# RefrigeradorLG.net
KiCad netlist of a schematic drawn in EAGLE
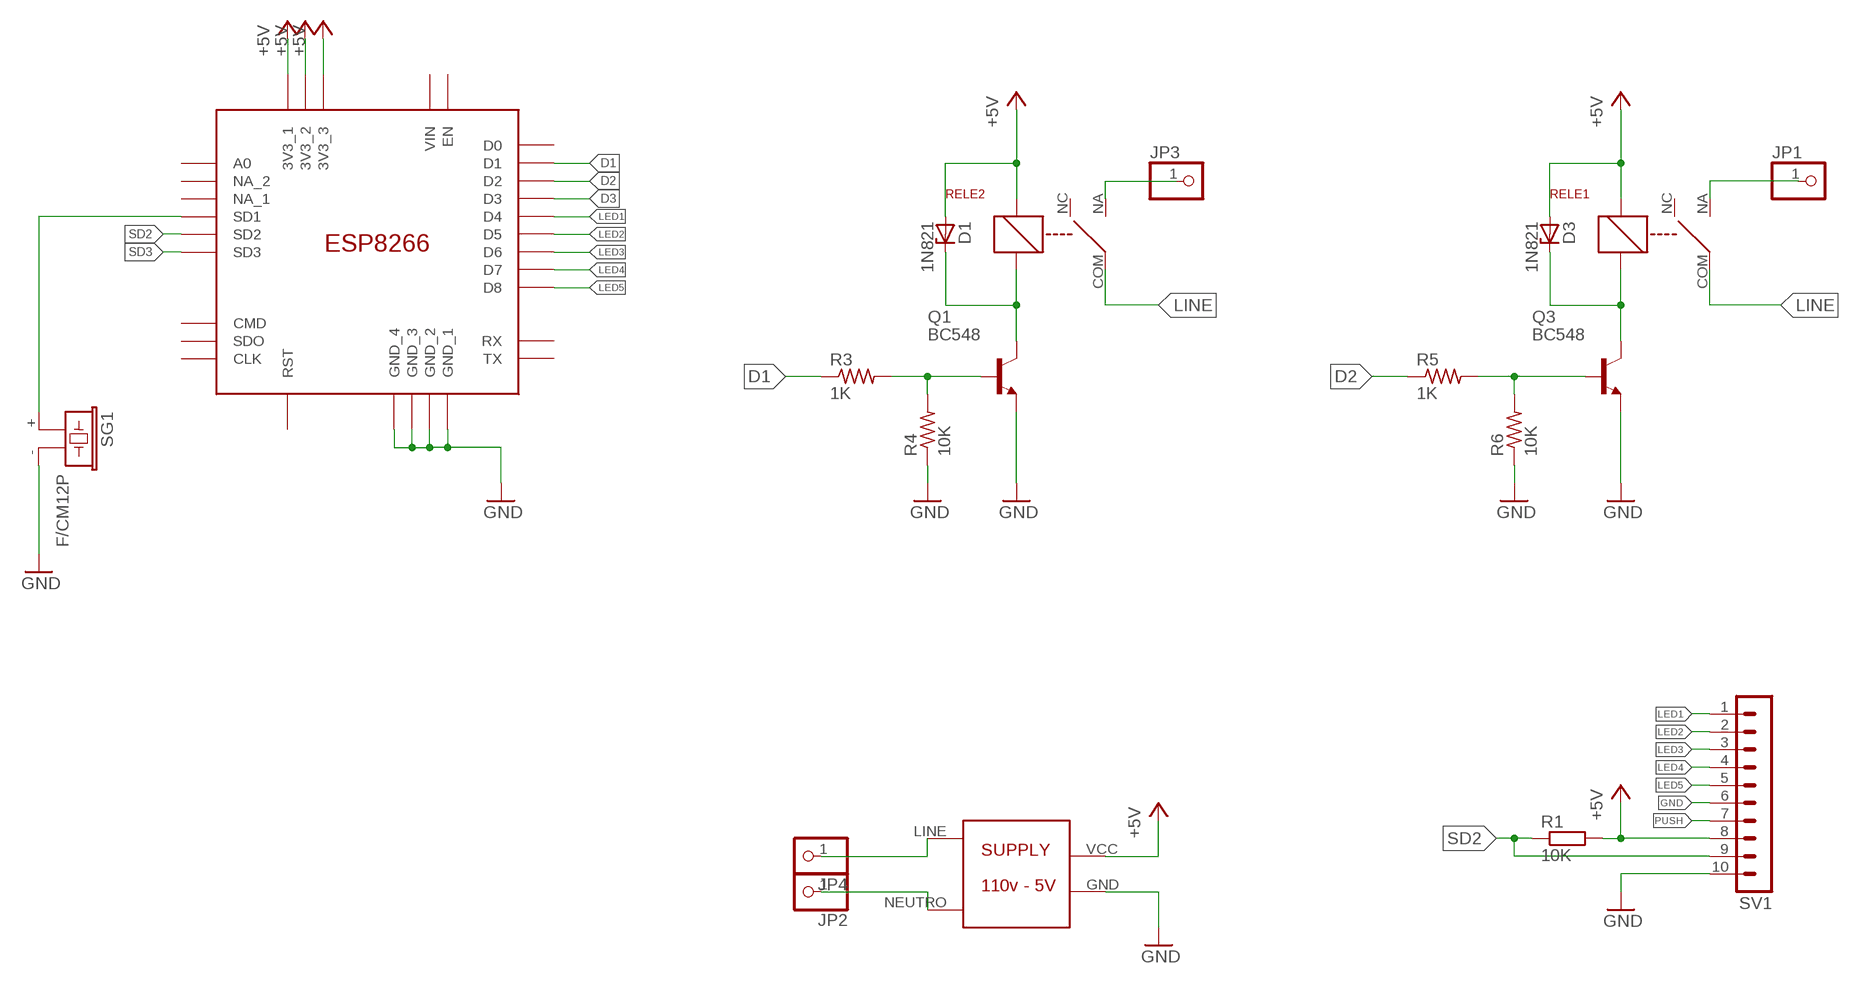
[diagram p0: schematic, sheet 1]

(export (version "E")
  (design (tool "Eeschema 10.0.6"))
  (components
    (comp (ref "D1")
      (value "1N821")
      (footprint "eagle-import:DO35Z10")
      (libsource (lib "eagle-import") (part "1N821"))
    )
    (comp (ref "D3")
      (value "1N821")
      (footprint "eagle-import:DO35Z10")
      (libsource (lib "eagle-import") (part "1N821"))
    )
    (comp (ref "ESP8266")
      (value "ESP8266")
      (footprint "eagle-import:ESP8266")
      (libsource (lib "eagle-import") (part "ESP8266"))
    )
    (comp (ref "JP1")
      (value "PINHD-1X1")
      (footprint "eagle-import:1X01")
      (libsource (lib "eagle-import") (part "PINHD-1X1"))
    )
    (comp (ref "JP2")
      (value "PINHD-1X1")
      (footprint "eagle-import:1X01")
      (libsource (lib "eagle-import") (part "PINHD-1X1"))
    )
    (comp (ref "JP3")
      (value "PINHD-1X1")
      (footprint "eagle-import:1X01")
      (libsource (lib "eagle-import") (part "PINHD-1X1"))
    )
    (comp (ref "JP4")
      (value "PINHD-1X1")
      (footprint "eagle-import:1X01")
      (libsource (lib "eagle-import") (part "PINHD-1X1"))
    )
    (comp (ref "Q1")
      (value "BC548")
      (footprint "eagle-import:TO92-EBC")
      (libsource (lib "eagle-import") (part "BC548"))
    )
    (comp (ref "Q3")
      (value "BC548")
      (footprint "eagle-import:TO92-EBC")
      (libsource (lib "eagle-import") (part "BC548"))
    )
    (comp (ref "R1")
      (value "10K")
      (footprint "eagle-import:0204_7")
      (libsource (lib "eagle-import") (part "R-EU_0204/7"))
    )
    (comp (ref "R3")
      (value "1K")
      (footprint "eagle-import:0204_7")
      (libsource (lib "eagle-import") (part "R-US_0204/7"))
    )
    (comp (ref "R4")
      (value "10K")
      (footprint "eagle-import:0204_7")
      (libsource (lib "eagle-import") (part "R-US_0204/7"))
    )
    (comp (ref "R5")
      (value "1K")
      (footprint "eagle-import:0204_7")
      (libsource (lib "eagle-import") (part "R-US_0204/7"))
    )
    (comp (ref "R6")
      (value "10K")
      (footprint "eagle-import:0204_7")
      (libsource (lib "eagle-import") (part "R-US_0204/7"))
    )
    (comp (ref "RELE1")
      (value "RAS0510")
      (footprint "eagle-import:RAS0510")
      (libsource (lib "eagle-import") (part "RAS0510"))
    )
    (comp (ref "RELE2")
      (value "RAS0510")
      (footprint "eagle-import:RAS0510")
      (libsource (lib "eagle-import") (part "RAS0510"))
    )
    (comp (ref "SG1")
      (value "F/CM12P")
      (footprint "eagle-import:F_CM12P")
      (libsource (lib "eagle-import") (part "F/CM12P"))
    )
    (comp (ref "SV1")
      (value "MA10-1")
      (footprint "eagle-import:MA10-1")
      (libsource (lib "eagle-import") (part "MA10-1"))
    )
    (comp (ref "U$1")
      (value "SUPPLY5V")
      (footprint "eagle-import:SUPPLY5V")
      (libsource (lib "eagle-import") (part "SUPPLY5V"))
    )
  )
  (nets
    (net (code "1") (name "+5V") (class "Default")
      (node (ref "D1") (pin "A") (pinfunction "A_A") (pintype "passive"))
      (node (ref "D3") (pin "A") (pinfunction "A_A") (pintype "passive"))
      (node (ref "ESP8266") (pin "3V3_1") (pinfunction "3V3_1_3V3_1") (pintype "bidirectional"))
      (node (ref "ESP8266") (pin "3V3_2") (pinfunction "3V3_2_3V3_2") (pintype "bidirectional"))
      (node (ref "ESP8266") (pin "3V3_3") (pinfunction "3V3_3_3V3_3") (pintype "bidirectional"))
      (node (ref "R1") (pin "2") (pinfunction "2_2") (pintype "passive"))
      (node (ref "RELE1") (pin "B1") (pinfunction "B1_B1") (pintype "bidirectional"))
      (node (ref "RELE2") (pin "B1") (pinfunction "B1_B1") (pintype "bidirectional"))
      (node (ref "SV1") (pin "8") (pinfunction "8_8") (pintype "passive"))
      (node (ref "U$1") (pin "VCC") (pinfunction "VCC_VCC") (pintype "bidirectional"))
    )
    (net (code "2") (name "D1") (class "Default")
      (node (ref "ESP8266") (pin "D1") (pinfunction "D1_D1") (pintype "bidirectional"))
      (node (ref "R3") (pin "1") (pinfunction "1_1") (pintype "passive"))
    )
    (net (code "3") (name "D2") (class "Default")
      (node (ref "ESP8266") (pin "D2") (pinfunction "D2_D2") (pintype "bidirectional"))
      (node (ref "R5") (pin "1") (pinfunction "1_1") (pintype "passive"))
    )
    (net (code "4") (name "D3") (class "Default")
      (node (ref "ESP8266") (pin "D3") (pinfunction "D3_D3") (pintype "bidirectional"))
    )
    (net (code "5") (name "GND") (class "Default")
      (node (ref "ESP8266") (pin "GND_1") (pinfunction "GND_1_GND_1") (pintype "bidirectional"))
      (node (ref "ESP8266") (pin "GND_2") (pinfunction "GND_2_GND_2") (pintype "bidirectional"))
      (node (ref "ESP8266") (pin "GND_3") (pinfunction "GND_3_GND_3") (pintype "bidirectional"))
      (node (ref "ESP8266") (pin "GND_4") (pinfunction "GND_4_GND_4") (pintype "bidirectional"))
      (node (ref "Q1") (pin "E") (pinfunction "E_E") (pintype "passive"))
      (node (ref "Q3") (pin "E") (pinfunction "E_E") (pintype "passive"))
      (node (ref "R4") (pin "1") (pinfunction "1_1") (pintype "passive"))
      (node (ref "R6") (pin "1") (pinfunction "1_1") (pintype "passive"))
      (node (ref "SG1") (pin "-") (pinfunction "2_-") (pintype "passive"))
      (node (ref "SV1") (pin "10") (pinfunction "10_10") (pintype "passive"))
      (node (ref "SV1") (pin "6") (pinfunction "6_6") (pintype "passive"))
      (node (ref "U$1") (pin "GND") (pinfunction "GND_GND") (pintype "bidirectional"))
    )
    (net (code "6") (name "LED1") (class "Default")
      (node (ref "ESP8266") (pin "D4") (pinfunction "D4_D4") (pintype "bidirectional"))
      (node (ref "SV1") (pin "1") (pinfunction "1_1") (pintype "passive"))
    )
    (net (code "7") (name "LED2") (class "Default")
      (node (ref "ESP8266") (pin "D5") (pinfunction "D5_D5") (pintype "bidirectional"))
      (node (ref "SV1") (pin "2") (pinfunction "2_2") (pintype "passive"))
    )
    (net (code "8") (name "LED3") (class "Default")
      (node (ref "ESP8266") (pin "D6") (pinfunction "D6_D6") (pintype "bidirectional"))
      (node (ref "SV1") (pin "3") (pinfunction "3_3") (pintype "passive"))
    )
    (net (code "9") (name "LED4") (class "Default")
      (node (ref "ESP8266") (pin "D7") (pinfunction "D7_D7") (pintype "bidirectional"))
      (node (ref "SV1") (pin "4") (pinfunction "4_4") (pintype "passive"))
    )
    (net (code "10") (name "LED5") (class "Default")
      (node (ref "ESP8266") (pin "D8") (pinfunction "D8_D8") (pintype "bidirectional"))
      (node (ref "SV1") (pin "5") (pinfunction "5_5") (pintype "passive"))
    )
    (net (code "11") (name "LINE") (class "Default")
      (node (ref "JP4") (pin "1") (pinfunction "1_1") (pintype "passive"))
      (node (ref "RELE1") (pin "COM") (pinfunction "COM_COM") (pintype "bidirectional"))
      (node (ref "RELE2") (pin "COM") (pinfunction "COM_COM") (pintype "bidirectional"))
      (node (ref "U$1") (pin "LINE") (pinfunction "LINE_LINE") (pintype "bidirectional"))
    )
    (net (code "12") (name "Net-(D1-PadC)") (class "Default")
      (node (ref "D1") (pin "C") (pinfunction "C_C") (pintype "passive"))
      (node (ref "Q1") (pin "C") (pinfunction "C_C") (pintype "passive"))
      (node (ref "RELE2") (pin "B2") (pinfunction "B2_B2") (pintype "bidirectional"))
    )
    (net (code "13") (name "Net-(D3-PadC)") (class "Default")
      (node (ref "D3") (pin "C") (pinfunction "C_C") (pintype "passive"))
      (node (ref "Q3") (pin "C") (pinfunction "C_C") (pintype "passive"))
      (node (ref "RELE1") (pin "B2") (pinfunction "B2_B2") (pintype "bidirectional"))
    )
    (net (code "14") (name "Net-(JP1-Pad1)") (class "Default")
      (node (ref "JP1") (pin "1") (pinfunction "1_1") (pintype "passive"))
      (node (ref "RELE1") (pin "NA") (pinfunction "NA_NA") (pintype "bidirectional"))
    )
    (net (code "15") (name "Net-(JP2-Pad1)") (class "Default")
      (node (ref "JP2") (pin "1") (pinfunction "1_1") (pintype "passive"))
      (node (ref "U$1") (pin "NEUTRO") (pinfunction "NEUTRO_NEUTRO") (pintype "bidirectional"))
    )
    (net (code "16") (name "Net-(JP3-Pad1)") (class "Default")
      (node (ref "JP3") (pin "1") (pinfunction "1_1") (pintype "passive"))
      (node (ref "RELE2") (pin "NA") (pinfunction "NA_NA") (pintype "bidirectional"))
    )
    (net (code "17") (name "Net-(Q1-PadB)") (class "Default")
      (node (ref "Q1") (pin "B") (pinfunction "B_B") (pintype "passive"))
      (node (ref "R3") (pin "2") (pinfunction "2_2") (pintype "passive"))
      (node (ref "R4") (pin "2") (pinfunction "2_2") (pintype "passive"))
    )
    (net (code "18") (name "Net-(Q3-PadB)") (class "Default")
      (node (ref "Q3") (pin "B") (pinfunction "B_B") (pintype "passive"))
      (node (ref "R5") (pin "2") (pinfunction "2_2") (pintype "passive"))
      (node (ref "R6") (pin "2") (pinfunction "2_2") (pintype "passive"))
    )
    (net (code "19") (name "Net-(SG1-1)") (class "Default")
      (node (ref "ESP8266") (pin "SD1") (pinfunction "SD1_SD1") (pintype "bidirectional"))
      (node (ref "SG1") (pin "+") (pinfunction "1_+") (pintype "passive"))
    )
    (net (code "20") (name "PUSH") (class "Default")
      (node (ref "SV1") (pin "7") (pinfunction "7_7") (pintype "passive"))
    )
    (net (code "21") (name "SD2") (class "Default")
      (node (ref "ESP8266") (pin "SD2") (pinfunction "SD2_SD2") (pintype "bidirectional"))
      (node (ref "R1") (pin "1") (pinfunction "1_1") (pintype "passive"))
      (node (ref "SV1") (pin "9") (pinfunction "9_9") (pintype "passive"))
    )
    (net (code "22") (name "SD3") (class "Default")
      (node (ref "ESP8266") (pin "SD3") (pinfunction "SD3_SD3") (pintype "bidirectional"))
    )
    (net (code "23") (name "unconnected-(ESP8266-PadA0)") (class "Default")
      (node (ref "ESP8266") (pin "A0") (pinfunction "A0_A0") (pintype "bidirectional"))
    )
    (net (code "24") (name "unconnected-(ESP8266-PadCLK)") (class "Default")
      (node (ref "ESP8266") (pin "CLK") (pinfunction "CLK_CLK") (pintype "bidirectional"))
    )
    (net (code "25") (name "unconnected-(ESP8266-PadCMD)") (class "Default")
      (node (ref "ESP8266") (pin "CMD") (pinfunction "CMD_CMD") (pintype "bidirectional"))
    )
    (net (code "26") (name "unconnected-(ESP8266-PadD0)") (class "Default")
      (node (ref "ESP8266") (pin "D0") (pinfunction "D0_D0") (pintype "bidirectional"))
    )
    (net (code "27") (name "unconnected-(ESP8266-PadEN)") (class "Default")
      (node (ref "ESP8266") (pin "EN") (pinfunction "EN_EN") (pintype "bidirectional"))
    )
    (net (code "28") (name "unconnected-(ESP8266-PadNA_1)") (class "Default")
      (node (ref "ESP8266") (pin "NA_1") (pinfunction "NA_1_NA_1") (pintype "bidirectional"))
    )
    (net (code "29") (name "unconnected-(ESP8266-PadNA_2)") (class "Default")
      (node (ref "ESP8266") (pin "NA_2") (pinfunction "NA_2_NA_2") (pintype "bidirectional"))
    )
    (net (code "30") (name "unconnected-(ESP8266-PadRST)") (class "Default")
      (node (ref "ESP8266") (pin "RST") (pinfunction "RST_RST") (pintype "bidirectional"))
    )
    (net (code "31") (name "unconnected-(ESP8266-PadRX)") (class "Default")
      (node (ref "ESP8266") (pin "RX") (pinfunction "RX_RX") (pintype "bidirectional"))
    )
    (net (code "32") (name "unconnected-(ESP8266-PadSDO)") (class "Default")
      (node (ref "ESP8266") (pin "SDO") (pinfunction "SDO_SDO") (pintype "bidirectional"))
    )
    (net (code "33") (name "unconnected-(ESP8266-PadTX)") (class "Default")
      (node (ref "ESP8266") (pin "TX") (pinfunction "TX_TX") (pintype "bidirectional"))
    )
    (net (code "34") (name "unconnected-(ESP8266-PadVIN)") (class "Default")
      (node (ref "ESP8266") (pin "VIN") (pinfunction "VIN_VIN") (pintype "bidirectional"))
    )
    (net (code "35") (name "unconnected-(RELE1-PadNC)") (class "Default")
      (node (ref "RELE1") (pin "NC") (pinfunction "NC_NC") (pintype "bidirectional"))
    )
    (net (code "36") (name "unconnected-(RELE2-PadNC)") (class "Default")
      (node (ref "RELE2") (pin "NC") (pinfunction "NC_NC") (pintype "bidirectional"))
    )
  )
)
